# Power.net
KiCad netlist of a schematic drawn in Altium Designer
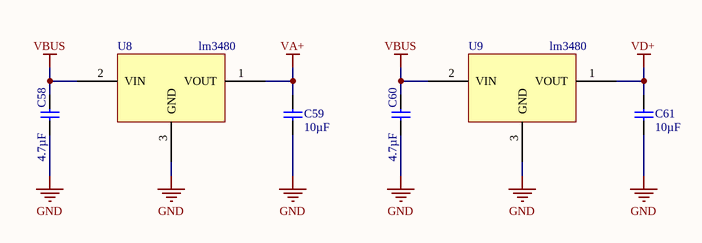
[diagram p0: Power.SchDoc]

(export (version "E")
  (design (tool "Eeschema 10.0.6"))
  (components
    (comp (ref "C58")
      (value "4.7µF")
      (footprint "0805")
      (description "Chip Cap 0805")
      (fields (field (name "PART NUMBER") "C0805-4µ7") (field (name "PUBLISHER") "Nordic Semiconductor"))
      (libsource (lib "Nordic Passive DB") (part "CAP"))
    )
    (comp (ref "C59")
      (value "10µF")
      (footprint "0805")
      (description "Chip Cap 0805")
      (fields (field (name "PART NUMBER") "C0805-10µ") (field (name "PUBLISHER") "Nordic Semiconductor"))
      (libsource (lib "Nordic Passive DB") (part "CAP"))
    )
    (comp (ref "C60")
      (value "4.7µF")
      (footprint "0805")
      (description "Chip Cap 0805")
      (fields (field (name "PART NUMBER") "C0805-4µ7") (field (name "PUBLISHER") "Nordic Semiconductor"))
      (libsource (lib "Nordic Passive DB") (part "CAP"))
    )
    (comp (ref "C61")
      (value "10µF")
      (footprint "0805")
      (description "Chip Cap 0805")
      (fields (field (name "PART NUMBER") "C0805-10µ") (field (name "PUBLISHER") "Nordic Semiconductor"))
      (libsource (lib "Nordic Passive DB") (part "CAP"))
    )
    (comp (ref "U8")
      (value "lm3480")
      (footprint "SOT95P237X112-3N")
      (libsource (lib "nRF2460") (part "lm3480"))
    )
    (comp (ref "U9")
      (value "lm3480")
      (footprint "SOT95P237X112-3N")
      (libsource (lib "nRF2460") (part "lm3480"))
    )
  )
  (nets
    (net (code "1") (name "GND") (class "Default")
      (node (ref "C58") (pin "1") (pinfunction "1_1") (pintype "passive"))
      (node (ref "C59") (pin "1") (pinfunction "1_1") (pintype "passive"))
      (node (ref "C60") (pin "1") (pinfunction "1_1") (pintype "passive"))
      (node (ref "C61") (pin "1") (pinfunction "1_1") (pintype "passive"))
      (node (ref "U8") (pin "3") (pinfunction "GND_3") (pintype "passive"))
      (node (ref "U9") (pin "3") (pinfunction "GND_3") (pintype "passive"))
    )
    (net (code "2") (name "VA+") (class "Default")
      (node (ref "C59") (pin "2") (pinfunction "2_2") (pintype "passive"))
      (node (ref "U8") (pin "1") (pinfunction "VOUT_1") (pintype "passive"))
    )
    (net (code "3") (name "VBUS") (class "Default")
      (node (ref "C58") (pin "2") (pinfunction "2_2") (pintype "passive"))
      (node (ref "C60") (pin "2") (pinfunction "2_2") (pintype "passive"))
      (node (ref "U8") (pin "2") (pinfunction "VIN_2") (pintype "passive"))
      (node (ref "U9") (pin "2") (pinfunction "VIN_2") (pintype "passive"))
    )
    (net (code "4") (name "VD+") (class "Default")
      (node (ref "C61") (pin "2") (pinfunction "2_2") (pintype "passive"))
      (node (ref "U9") (pin "1") (pinfunction "VOUT_1") (pintype "passive"))
    )
  )
)
